# hex_bin_eeprom_display.net
KiCad netlist of a schematic drawn in EAGLE
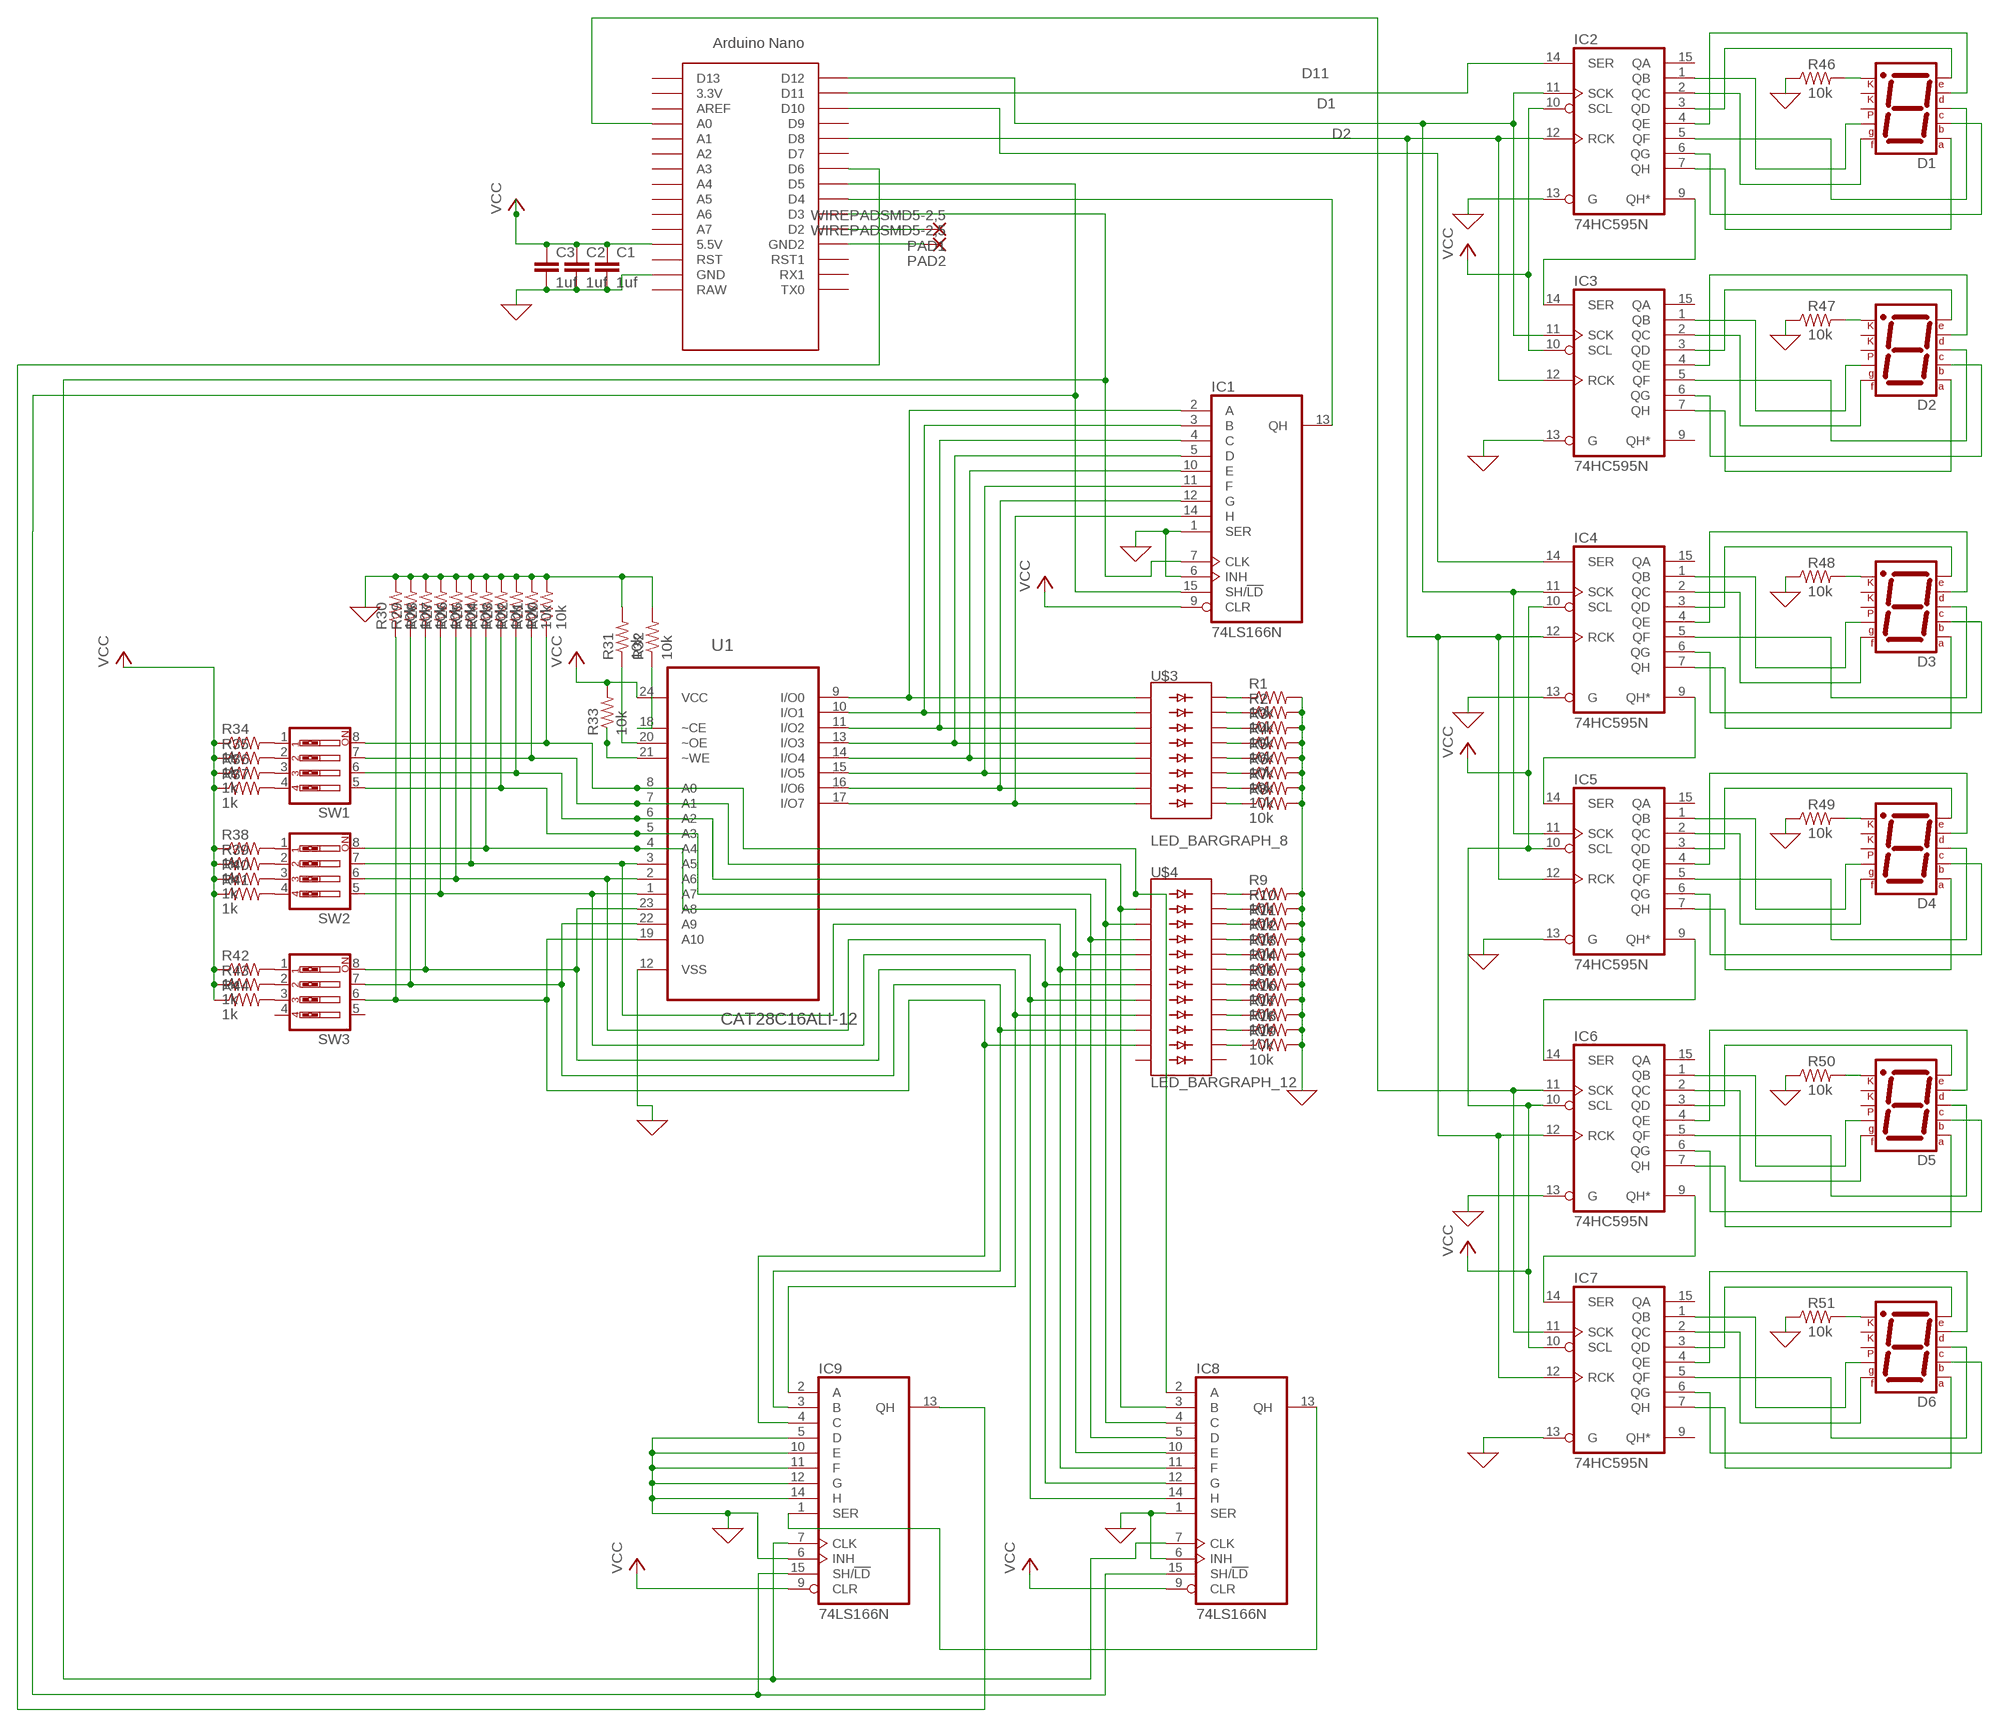
[diagram p0: schematic, sheet 1]

(export (version "E")
  (design (tool "Eeschema 10.0.6"))
  (components
    (comp (ref "C1")
      (value "1uf")
      (footprint "eagle-import:C5B3")
      (libsource (lib "eagle-import") (part "C5/3"))
    )
    (comp (ref "C2")
      (value "1uf")
      (footprint "eagle-import:C5B3")
      (libsource (lib "eagle-import") (part "C5/3"))
    )
    (comp (ref "C3")
      (value "1uf")
      (footprint "eagle-import:C5B3")
      (libsource (lib "eagle-import") (part "C5/3"))
    )
    (comp (ref "D1")
      (value "7SEG-CK")
      (footprint "eagle-import:7SEG-13")
      (libsource (lib "eagle-import") (part "7SEG-CK"))
    )
    (comp (ref "D2")
      (value "7SEG-CK")
      (footprint "eagle-import:7SEG-13")
      (libsource (lib "eagle-import") (part "7SEG-CK"))
    )
    (comp (ref "D3")
      (value "7SEG-CK")
      (footprint "eagle-import:7SEG-13")
      (libsource (lib "eagle-import") (part "7SEG-CK"))
    )
    (comp (ref "D4")
      (value "7SEG-CK")
      (footprint "eagle-import:7SEG-13")
      (libsource (lib "eagle-import") (part "7SEG-CK"))
    )
    (comp (ref "D5")
      (value "7SEG-CK")
      (footprint "eagle-import:7SEG-13")
      (libsource (lib "eagle-import") (part "7SEG-CK"))
    )
    (comp (ref "D6")
      (value "7SEG-CK")
      (footprint "eagle-import:7SEG-13")
      (libsource (lib "eagle-import") (part "7SEG-CK"))
    )
    (comp (ref "IC1")
      (value "74LS166N")
      (footprint "eagle-import:DIL16")
      (libsource (lib "eagle-import") (part "74166NLS"))
    )
    (comp (ref "IC2")
      (value "74HC595N")
      (footprint "eagle-import:DIL16")
      (libsource (lib "eagle-import") (part "74595NHC"))
    )
    (comp (ref "IC3")
      (value "74HC595N")
      (footprint "eagle-import:DIL16")
      (libsource (lib "eagle-import") (part "74595NHC"))
    )
    (comp (ref "IC4")
      (value "74HC595N")
      (footprint "eagle-import:DIL16")
      (libsource (lib "eagle-import") (part "74595NHC"))
    )
    (comp (ref "IC5")
      (value "74HC595N")
      (footprint "eagle-import:DIL16")
      (libsource (lib "eagle-import") (part "74595NHC"))
    )
    (comp (ref "IC6")
      (value "74HC595N")
      (footprint "eagle-import:DIL16")
      (libsource (lib "eagle-import") (part "74595NHC"))
    )
    (comp (ref "IC7")
      (value "74HC595N")
      (footprint "eagle-import:DIL16")
      (libsource (lib "eagle-import") (part "74595NHC"))
    )
    (comp (ref "IC8")
      (value "74LS166N")
      (footprint "eagle-import:DIL16")
      (libsource (lib "eagle-import") (part "74166NLS"))
    )
    (comp (ref "IC9")
      (value "74LS166N")
      (footprint "eagle-import:DIL16")
      (libsource (lib "eagle-import") (part "74166NLS"))
    )
    (comp (ref "PAD1")
      (value "WIREPADSMD5-2,5")
      (footprint "eagle-import:5-2,5")
      (libsource (lib "eagle-import") (part "WIREPADSMD5-2,5"))
    )
    (comp (ref "PAD2")
      (value "WIREPADSMD5-2,5")
      (footprint "eagle-import:5-2,5")
      (libsource (lib "eagle-import") (part "WIREPADSMD5-2,5"))
    )
    (comp (ref "R1")
      (value "10k")
      (footprint "eagle-import:0204_7")
      (libsource (lib "eagle-import") (part "R-US_0204/7"))
    )
    (comp (ref "R2")
      (value "10k")
      (footprint "eagle-import:0204_7")
      (libsource (lib "eagle-import") (part "R-US_0204/7"))
    )
    (comp (ref "R3")
      (value "10k")
      (footprint "eagle-import:0204_7")
      (libsource (lib "eagle-import") (part "R-US_0204/7"))
    )
    (comp (ref "R4")
      (value "10k")
      (footprint "eagle-import:0204_7")
      (libsource (lib "eagle-import") (part "R-US_0204/7"))
    )
    (comp (ref "R5")
      (value "10k")
      (footprint "eagle-import:0204_7")
      (libsource (lib "eagle-import") (part "R-US_0204/7"))
    )
    (comp (ref "R6")
      (value "10k")
      (footprint "eagle-import:0204_7")
      (libsource (lib "eagle-import") (part "R-US_0204/7"))
    )
    (comp (ref "R7")
      (value "10k")
      (footprint "eagle-import:0204_7")
      (libsource (lib "eagle-import") (part "R-US_0204/7"))
    )
    (comp (ref "R8")
      (value "10k")
      (footprint "eagle-import:0204_7")
      (libsource (lib "eagle-import") (part "R-US_0204/7"))
    )
    (comp (ref "R9")
      (value "10k")
      (footprint "eagle-import:0204_7")
      (libsource (lib "eagle-import") (part "R-US_0204/7"))
    )
    (comp (ref "R10")
      (value "10k")
      (footprint "eagle-import:0204_7")
      (libsource (lib "eagle-import") (part "R-US_0204/7"))
    )
    (comp (ref "R11")
      (value "10k")
      (footprint "eagle-import:0204_7")
      (libsource (lib "eagle-import") (part "R-US_0204/7"))
    )
    (comp (ref "R12")
      (value "10k")
      (footprint "eagle-import:0204_7")
      (libsource (lib "eagle-import") (part "R-US_0204/7"))
    )
    (comp (ref "R13")
      (value "10k")
      (footprint "eagle-import:0204_7")
      (libsource (lib "eagle-import") (part "R-US_0204/7"))
    )
    (comp (ref "R14")
      (value "10k")
      (footprint "eagle-import:0204_7")
      (libsource (lib "eagle-import") (part "R-US_0204/7"))
    )
    (comp (ref "R15")
      (value "10k")
      (footprint "eagle-import:0204_7")
      (libsource (lib "eagle-import") (part "R-US_0204/7"))
    )
    (comp (ref "R16")
      (value "10k")
      (footprint "eagle-import:0204_7")
      (libsource (lib "eagle-import") (part "R-US_0204/7"))
    )
    (comp (ref "R17")
      (value "10k")
      (footprint "eagle-import:0204_7")
      (libsource (lib "eagle-import") (part "R-US_0204/7"))
    )
    (comp (ref "R18")
      (value "10k")
      (footprint "eagle-import:0204_7")
      (libsource (lib "eagle-import") (part "R-US_0204/7"))
    )
    (comp (ref "R19")
      (value "10k")
      (footprint "eagle-import:0204_7")
      (libsource (lib "eagle-import") (part "R-US_0204/7"))
    )
    (comp (ref "R20")
      (value "10k")
      (footprint "eagle-import:0204_7")
      (libsource (lib "eagle-import") (part "R-US_0204/7"))
    )
    (comp (ref "R21")
      (value "10k")
      (footprint "eagle-import:0204_7")
      (libsource (lib "eagle-import") (part "R-US_0204/7"))
    )
    (comp (ref "R22")
      (value "10k")
      (footprint "eagle-import:0204_7")
      (libsource (lib "eagle-import") (part "R-US_0204/7"))
    )
    (comp (ref "R23")
      (value "10k")
      (footprint "eagle-import:0204_7")
      (libsource (lib "eagle-import") (part "R-US_0204/7"))
    )
    (comp (ref "R24")
      (value "10k")
      (footprint "eagle-import:0204_7")
      (libsource (lib "eagle-import") (part "R-US_0204/7"))
    )
    (comp (ref "R25")
      (value "10k")
      (footprint "eagle-import:0204_7")
      (libsource (lib "eagle-import") (part "R-US_0204/7"))
    )
    (comp (ref "R26")
      (value "10k")
      (footprint "eagle-import:0204_7")
      (libsource (lib "eagle-import") (part "R-US_0204/7"))
    )
    (comp (ref "R27")
      (value "10k")
      (footprint "eagle-import:0204_7")
      (libsource (lib "eagle-import") (part "R-US_0204/7"))
    )
    (comp (ref "R28")
      (value "10k")
      (footprint "eagle-import:0204_7")
      (libsource (lib "eagle-import") (part "R-US_0204/7"))
    )
    (comp (ref "R29")
      (value "10k")
      (footprint "eagle-import:0204_7")
      (libsource (lib "eagle-import") (part "R-US_0204/7"))
    )
    (comp (ref "R30")
      (value "10k")
      (footprint "eagle-import:0204_7")
      (libsource (lib "eagle-import") (part "R-US_0204/7"))
    )
    (comp (ref "R31")
      (value "10k")
      (footprint "eagle-import:0204_7")
      (libsource (lib "eagle-import") (part "R-US_0204/7"))
    )
    (comp (ref "R32")
      (value "10k")
      (footprint "eagle-import:0204_7")
      (libsource (lib "eagle-import") (part "R-US_0204/7"))
    )
    (comp (ref "R33")
      (value "10k")
      (footprint "eagle-import:0204_7")
      (libsource (lib "eagle-import") (part "R-US_0204/7"))
    )
    (comp (ref "R34")
      (value "1k")
      (footprint "eagle-import:0204_7")
      (libsource (lib "eagle-import") (part "R-US_0204/7"))
    )
    (comp (ref "R35")
      (value "1k")
      (footprint "eagle-import:0204_7")
      (libsource (lib "eagle-import") (part "R-US_0204/7"))
    )
    (comp (ref "R36")
      (value "1k")
      (footprint "eagle-import:0204_7")
      (libsource (lib "eagle-import") (part "R-US_0204/7"))
    )
    (comp (ref "R37")
      (value "1k")
      (footprint "eagle-import:0204_7")
      (libsource (lib "eagle-import") (part "R-US_0204/7"))
    )
    (comp (ref "R38")
      (value "1k")
      (footprint "eagle-import:0204_7")
      (libsource (lib "eagle-import") (part "R-US_0204/7"))
    )
    (comp (ref "R39")
      (value "1k")
      (footprint "eagle-import:0204_7")
      (libsource (lib "eagle-import") (part "R-US_0204/7"))
    )
    (comp (ref "R40")
      (value "1k")
      (footprint "eagle-import:0204_7")
      (libsource (lib "eagle-import") (part "R-US_0204/7"))
    )
    (comp (ref "R41")
      (value "1k")
      (footprint "eagle-import:0204_7")
      (libsource (lib "eagle-import") (part "R-US_0204/7"))
    )
    (comp (ref "R42")
      (value "1k")
      (footprint "eagle-import:0204_7")
      (libsource (lib "eagle-import") (part "R-US_0204/7"))
    )
    (comp (ref "R43")
      (value "1k")
      (footprint "eagle-import:0204_7")
      (libsource (lib "eagle-import") (part "R-US_0204/7"))
    )
    (comp (ref "R44")
      (value "1k")
      (footprint "eagle-import:0204_7")
      (libsource (lib "eagle-import") (part "R-US_0204/7"))
    )
    (comp (ref "R46")
      (value "10k")
      (footprint "eagle-import:0204_7")
      (libsource (lib "eagle-import") (part "R-US_0204/7"))
    )
    (comp (ref "R47")
      (value "10k")
      (footprint "eagle-import:0204_7")
      (libsource (lib "eagle-import") (part "R-US_0204/7"))
    )
    (comp (ref "R48")
      (value "10k")
      (footprint "eagle-import:0204_7")
      (libsource (lib "eagle-import") (part "R-US_0204/7"))
    )
    (comp (ref "R49")
      (value "10k")
      (footprint "eagle-import:0204_7")
      (libsource (lib "eagle-import") (part "R-US_0204/7"))
    )
    (comp (ref "R50")
      (value "10k")
      (footprint "eagle-import:0204_7")
      (libsource (lib "eagle-import") (part "R-US_0204/7"))
    )
    (comp (ref "R51")
      (value "10k")
      (footprint "eagle-import:0204_7")
      (libsource (lib "eagle-import") (part "R-US_0204/7"))
    )
    (comp (ref "SW1")
      (value "SW_DIP-4")
      (footprint "eagle-import:EDG-04")
      (libsource (lib "eagle-import") (part "SW_DIP-4"))
    )
    (comp (ref "SW2")
      (value "SW_DIP-4")
      (footprint "eagle-import:EDG-04")
      (libsource (lib "eagle-import") (part "SW_DIP-4"))
    )
    (comp (ref "SW3")
      (value "SW_DIP-4")
      (footprint "eagle-import:EDG-04")
      (libsource (lib "eagle-import") (part "SW_DIP-4"))
    )
    (comp (ref "U$1")
      (value "NANO")
      (footprint "eagle-import:NANO")
      (libsource (lib "eagle-import") (part "NANO"))
    )
    (comp (ref "U$3")
      (value "LED_BARGRAPH_8")
      (footprint "eagle-import:LED_BARGRAPH_8")
      (libsource (lib "eagle-import") (part "LED_BARGRAPH_8"))
    )
    (comp (ref "U$4")
      (value "LED_BARGRAPH_12")
      (footprint "eagle-import:LED_BARGRAPH_12")
      (libsource (lib "eagle-import") (part "LED_BARGRAPH_12"))
    )
    (comp (ref "U1")
      (value "CAT28C16ALI-12")
      (footprint "eagle-import:DIP254P1524X635-24")
      (fields (field (name "MF") "ON Semiconductor") (field (name "MP") "CAT28C16ALI12"))
      (libsource (lib "eagle-import") (part "CAT28C16ALI-12"))
    )
  )
  (nets
    (net (code "1") (name "/D1") (class "Default")
      (node (ref "IC2") (pin "11") (pinfunction "SCK_11") (pintype "input"))
      (node (ref "IC3") (pin "11") (pinfunction "SCK_11") (pintype "input"))
      (node (ref "IC4") (pin "11") (pinfunction "SCK_11") (pintype "input"))
      (node (ref "IC5") (pin "11") (pinfunction "SCK_11") (pintype "input"))
      (node (ref "U$1") (pin "D12") (pinfunction "D12_D12") (pintype "bidirectional"))
    )
    (net (code "2") (name "/D2") (class "Default")
      (node (ref "IC2") (pin "12") (pinfunction "RCK_12") (pintype "input"))
      (node (ref "IC3") (pin "12") (pinfunction "RCK_12") (pintype "input"))
      (node (ref "IC4") (pin "12") (pinfunction "RCK_12") (pintype "input"))
      (node (ref "IC5") (pin "12") (pinfunction "RCK_12") (pintype "input"))
      (node (ref "IC6") (pin "12") (pinfunction "RCK_12") (pintype "input"))
      (node (ref "IC7") (pin "12") (pinfunction "RCK_12") (pintype "input"))
      (node (ref "U$1") (pin "D8") (pinfunction "D8_D8") (pintype "bidirectional"))
    )
    (net (code "3") (name "/D11") (class "Default")
      (node (ref "IC2") (pin "14") (pinfunction "SER_14") (pintype "input"))
      (node (ref "U$1") (pin "D11") (pinfunction "D11_D11") (pintype "bidirectional"))
    )
    (net (code "4") (name "GND") (class "Default")
      (node (ref "C1") (pin "2") (pinfunction "2_2") (pintype "passive"))
      (node (ref "C2") (pin "2") (pinfunction "2_2") (pintype "passive"))
      (node (ref "C3") (pin "2") (pinfunction "2_2") (pintype "passive"))
      (node (ref "IC1") (pin "1") (pinfunction "SER_1") (pintype "input"))
      (node (ref "IC1") (pin "6") (pinfunction "INH_6") (pintype "input"))
      (node (ref "IC2") (pin "13") (pinfunction "G_13") (pintype "input"))
      (node (ref "IC3") (pin "13") (pinfunction "G_13") (pintype "input"))
      (node (ref "IC4") (pin "13") (pinfunction "G_13") (pintype "input"))
      (node (ref "IC5") (pin "13") (pinfunction "G_13") (pintype "input"))
      (node (ref "IC6") (pin "13") (pinfunction "G_13") (pintype "input"))
      (node (ref "IC7") (pin "13") (pinfunction "G_13") (pintype "input"))
      (node (ref "IC8") (pin "1") (pinfunction "SER_1") (pintype "input"))
      (node (ref "IC8") (pin "6") (pinfunction "INH_6") (pintype "input"))
      (node (ref "IC9") (pin "10") (pinfunction "E_10") (pintype "input"))
      (node (ref "IC9") (pin "11") (pinfunction "F_11") (pintype "input"))
      (node (ref "IC9") (pin "12") (pinfunction "G_12") (pintype "input"))
      (node (ref "IC9") (pin "14") (pinfunction "H_14") (pintype "input"))
      (node (ref "IC9") (pin "5") (pinfunction "D_5") (pintype "input"))
      (node (ref "IC9") (pin "6") (pinfunction "INH_6") (pintype "input"))
      (node (ref "R1") (pin "2") (pinfunction "2_2") (pintype "passive"))
      (node (ref "R10") (pin "2") (pinfunction "2_2") (pintype "passive"))
      (node (ref "R11") (pin "2") (pinfunction "2_2") (pintype "passive"))
      (node (ref "R12") (pin "2") (pinfunction "2_2") (pintype "passive"))
      (node (ref "R13") (pin "2") (pinfunction "2_2") (pintype "passive"))
      (node (ref "R14") (pin "2") (pinfunction "2_2") (pintype "passive"))
      (node (ref "R15") (pin "2") (pinfunction "2_2") (pintype "passive"))
      (node (ref "R16") (pin "2") (pinfunction "2_2") (pintype "passive"))
      (node (ref "R17") (pin "2") (pinfunction "2_2") (pintype "passive"))
      (node (ref "R18") (pin "2") (pinfunction "2_2") (pintype "passive"))
      (node (ref "R19") (pin "2") (pinfunction "2_2") (pintype "passive"))
      (node (ref "R2") (pin "2") (pinfunction "2_2") (pintype "passive"))
      (node (ref "R20") (pin "2") (pinfunction "2_2") (pintype "passive"))
      (node (ref "R21") (pin "2") (pinfunction "2_2") (pintype "passive"))
      (node (ref "R22") (pin "2") (pinfunction "2_2") (pintype "passive"))
      (node (ref "R23") (pin "2") (pinfunction "2_2") (pintype "passive"))
      (node (ref "R24") (pin "2") (pinfunction "2_2") (pintype "passive"))
      (node (ref "R25") (pin "2") (pinfunction "2_2") (pintype "passive"))
      (node (ref "R26") (pin "2") (pinfunction "2_2") (pintype "passive"))
      (node (ref "R27") (pin "2") (pinfunction "2_2") (pintype "passive"))
      (node (ref "R28") (pin "2") (pinfunction "2_2") (pintype "passive"))
      (node (ref "R29") (pin "2") (pinfunction "2_2") (pintype "passive"))
      (node (ref "R3") (pin "2") (pinfunction "2_2") (pintype "passive"))
      (node (ref "R30") (pin "2") (pinfunction "2_2") (pintype "passive"))
      (node (ref "R31") (pin "2") (pinfunction "2_2") (pintype "passive"))
      (node (ref "R32") (pin "2") (pinfunction "2_2") (pintype "passive"))
      (node (ref "R4") (pin "2") (pinfunction "2_2") (pintype "passive"))
      (node (ref "R46") (pin "1") (pinfunction "1_1") (pintype "passive"))
      (node (ref "R47") (pin "1") (pinfunction "1_1") (pintype "passive"))
      (node (ref "R48") (pin "1") (pinfunction "1_1") (pintype "passive"))
      (node (ref "R49") (pin "1") (pinfunction "1_1") (pintype "passive"))
      (node (ref "R5") (pin "2") (pinfunction "2_2") (pintype "passive"))
      (node (ref "R50") (pin "1") (pinfunction "1_1") (pintype "passive"))
      (node (ref "R51") (pin "1") (pinfunction "1_1") (pintype "passive"))
      (node (ref "R6") (pin "2") (pinfunction "2_2") (pintype "passive"))
      (node (ref "R7") (pin "2") (pinfunction "2_2") (pintype "passive"))
      (node (ref "R8") (pin "2") (pinfunction "2_2") (pintype "passive"))
      (node (ref "R9") (pin "2") (pinfunction "2_2") (pintype "passive"))
      (node (ref "U$1") (pin "GND") (pinfunction "GND_GND") (pintype "bidirectional"))
      (node (ref "U1") (pin "12") (pinfunction "VSS_12") (pintype "power_in"))
    )
    (net (code "5") (name "Net-(D1-A)") (class "Default")
      (node (ref "D1") (pin "7") (pinfunction "A_7") (pintype "passive"))
      (node (ref "IC2") (pin "7") (pinfunction "QH_7") (pintype "tri_state"))
    )
    (net (code "6") (name "Net-(D1-B)") (class "Default")
      (node (ref "D1") (pin "6") (pinfunction "B_6") (pintype "passive"))
      (node (ref "IC2") (pin "6") (pinfunction "QG_6") (pintype "tri_state"))
    )
    (net (code "7") (name "Net-(D1-C)") (class "Default")
      (node (ref "D1") (pin "4") (pinfunction "C_4") (pintype "passive"))
      (node (ref "IC2") (pin "5") (pinfunction "QF_5") (pintype "tri_state"))
    )
    (net (code "8") (name "Net-(D1-CK2)") (class "Default")
      (node (ref "D1") (pin "8") (pinfunction "CK2_8") (pintype "passive"))
      (node (ref "R46") (pin "2") (pinfunction "2_2") (pintype "passive"))
    )
    (net (code "9") (name "Net-(D1-D)") (class "Default")
      (node (ref "D1") (pin "2") (pinfunction "D_2") (pintype "passive"))
      (node (ref "IC2") (pin "4") (pinfunction "QE_4") (pintype "tri_state"))
    )
    (net (code "10") (name "Net-(D1-E)") (class "Default")
      (node (ref "D1") (pin "1") (pinfunction "E_1") (pintype "passive"))
      (node (ref "IC2") (pin "3") (pinfunction "QD_3") (pintype "tri_state"))
    )
    (net (code "11") (name "Net-(D1-F)") (class "Default")
      (node (ref "D1") (pin "9") (pinfunction "F_9") (pintype "passive"))
      (node (ref "IC2") (pin "2") (pinfunction "QC_2") (pintype "tri_state"))
    )
    (net (code "12") (name "Net-(D1-G)") (class "Default")
      (node (ref "D1") (pin "10") (pinfunction "G_10") (pintype "passive"))
      (node (ref "IC2") (pin "1") (pinfunction "QB_1") (pintype "tri_state"))
    )
    (net (code "13") (name "Net-(D2-A)") (class "Default")
      (node (ref "D2") (pin "7") (pinfunction "A_7") (pintype "passive"))
      (node (ref "IC3") (pin "7") (pinfunction "QH_7") (pintype "tri_state"))
    )
    (net (code "14") (name "Net-(D2-B)") (class "Default")
      (node (ref "D2") (pin "6") (pinfunction "B_6") (pintype "passive"))
      (node (ref "IC3") (pin "6") (pinfunction "QG_6") (pintype "tri_state"))
    )
    (net (code "15") (name "Net-(D2-C)") (class "Default")
      (node (ref "D2") (pin "4") (pinfunction "C_4") (pintype "passive"))
      (node (ref "IC3") (pin "5") (pinfunction "QF_5") (pintype "tri_state"))
    )
    (net (code "16") (name "Net-(D2-CK2)") (class "Default")
      (node (ref "D2") (pin "8") (pinfunction "CK2_8") (pintype "passive"))
      (node (ref "R47") (pin "2") (pinfunction "2_2") (pintype "passive"))
    )
    (net (code "17") (name "Net-(D2-D)") (class "Default")
      (node (ref "D2") (pin "2") (pinfunction "D_2") (pintype "passive"))
      (node (ref "IC3") (pin "4") (pinfunction "QE_4") (pintype "tri_state"))
    )
    (net (code "18") (name "Net-(D2-E)") (class "Default")
      (node (ref "D2") (pin "1") (pinfunction "E_1") (pintype "passive"))
      (node (ref "IC3") (pin "3") (pinfunction "QD_3") (pintype "tri_state"))
    )
    (net (code "19") (name "Net-(D2-F)") (class "Default")
      (node (ref "D2") (pin "9") (pinfunction "F_9") (pintype "passive"))
      (node (ref "IC3") (pin "2") (pinfunction "QC_2") (pintype "tri_state"))
    )
    (net (code "20") (name "Net-(D2-G)") (class "Default")
      (node (ref "D2") (pin "10") (pinfunction "G_10") (pintype "passive"))
      (node (ref "IC3") (pin "1") (pinfunction "QB_1") (pintype "tri_state"))
    )
    (net (code "21") (name "Net-(D3-A)") (class "Default")
      (node (ref "D3") (pin "7") (pinfunction "A_7") (pintype "passive"))
      (node (ref "IC4") (pin "7") (pinfunction "QH_7") (pintype "tri_state"))
    )
    (net (code "22") (name "Net-(D3-B)") (class "Default")
      (node (ref "D3") (pin "6") (pinfunction "B_6") (pintype "passive"))
      (node (ref "IC4") (pin "6") (pinfunction "QG_6") (pintype "tri_state"))
    )
    (net (code "23") (name "Net-(D3-C)") (class "Default")
      (node (ref "D3") (pin "4") (pinfunction "C_4") (pintype "passive"))
      (node (ref "IC4") (pin "5") (pinfunction "QF_5") (pintype "tri_state"))
    )
    (net (code "24") (name "Net-(D3-CK2)") (class "Default")
      (node (ref "D3") (pin "8") (pinfunction "CK2_8") (pintype "passive"))
      (node (ref "R48") (pin "2") (pinfunction "2_2") (pintype "passive"))
    )
    (net (code "25") (name "Net-(D3-D)") (class "Default")
      (node (ref "D3") (pin "2") (pinfunction "D_2") (pintype "passive"))
      (node (ref "IC4") (pin "4") (pinfunction "QE_4") (pintype "tri_state"))
    )
    (net (code "26") (name "Net-(D3-E)") (class "Default")
      (node (ref "D3") (pin "1") (pinfunction "E_1") (pintype "passive"))
      (node (ref "IC4") (pin "3") (pinfunction "QD_3") (pintype "tri_state"))
    )
    (net (code "27") (name "Net-(D3-F)") (class "Default")
      (node (ref "D3") (pin "9") (pinfunction "F_9") (pintype "passive"))
      (node (ref "IC4") (pin "2") (pinfunction "QC_2") (pintype "tri_state"))
    )
    (net (code "28") (name "Net-(D3-G)") (class "Default")
      (node (ref "D3") (pin "10") (pinfunction "G_10") (pintype "passive"))
      (node (ref "IC4") (pin "1") (pinfunction "QB_1") (pintype "tri_state"))
    )
    (net (code "29") (name "Net-(D4-A)") (class "Default")
      (node (ref "D4") (pin "7") (pinfunction "A_7") (pintype "passive"))
      (node (ref "IC5") (pin "7") (pinfunction "QH_7") (pintype "tri_state"))
    )
    (net (code "30") (name "Net-(D4-B)") (class "Default")
      (node (ref "D4") (pin "6") (pinfunction "B_6") (pintype "passive"))
      (node (ref "IC5") (pin "6") (pinfunction "QG_6") (pintype "tri_state"))
    )
    (net (code "31") (name "Net-(D4-C)") (class "Default")
      (node (ref "D4") (pin "4") (pinfunction "C_4") (pintype "passive"))
      (node (ref "IC5") (pin "5") (pinfunction "QF_5") (pintype "tri_state"))
    )
    (net (code "32") (name "Net-(D4-CK2)") (class "Default")
      (node (ref "D4") (pin "8") (pinfunction "CK2_8") (pintype "passive"))
      (node (ref "R49") (pin "2") (pinfunction "2_2") (pintype "passive"))
    )
    (net (code "33") (name "Net-(D4-D)") (class "Default")
      (node (ref "D4") (pin "2") (pinfunction "D_2") (pintype "passive"))
      (node (ref "IC5") (pin "4") (pinfunction "QE_4") (pintype "tri_state"))
    )
    (net (code "34") (name "Net-(D4-E)") (class "Default")
      (node (ref "D4") (pin "1") (pinfunction "E_1") (pintype "passive"))
      (node (ref "IC5") (pin "3") (pinfunction "QD_3") (pintype "tri_state"))
    )
    (net (code "35") (name "Net-(D4-F)") (class "Default")
      (node (ref "D4") (pin "9") (pinfunction "F_9") (pintype "passive"))
      (node (ref "IC5") (pin "2") (pinfunction "QC_2") (pintype "tri_state"))
    )
    (net (code "36") (name "Net-(D4-G)") (class "Default")
      (node (ref "D4") (pin "10") (pinfunction "G_10") (pintype "passive"))
      (node (ref "IC5") (pin "1") (pinfunction "QB_1") (pintype "tri_state"))
    )
    (net (code "37") (name "Net-(D5-A)") (class "Default")
      (node (ref "D5") (pin "7") (pinfunction "A_7") (pintype "passive"))
      (node (ref "IC6") (pin "7") (pinfunction "QH_7") (pintype "tri_state"))
    )
    (net (code "38") (name "Net-(D5-B)") (class "Default")
      (node (ref "D5") (pin "6") (pinfunction "B_6") (pintype "passive"))
      (node (ref "IC6") (pin "6") (pinfunction "QG_6") (pintype "tri_state"))
    )
    (net (code "39") (name "Net-(D5-C)") (class "Default")
      (node (ref "D5") (pin "4") (pinfunction "C_4") (pintype "passive"))
      (node (ref "IC6") (pin "5") (pinfunction "QF_5") (pintype "tri_state"))
    )
    (net (code "40") (name "Net-(D5-CK2)") (class "Default")
      (node (ref "D5") (pin "8") (pinfunction "CK2_8") (pintype "passive"))
      (node (ref "R50") (pin "2") (pinfunction "2_2") (pintype "passive"))
    )
    (net (code "41") (name "Net-(D5-D)") (class "Default")
      (node (ref "D5") (pin "2") (pinfunction "D_2") (pintype "passive"))
      (node (ref "IC6") (pin "4") (pinfunction "QE_4") (pintype "tri_state"))
    )
    (net (code "42") (name "Net-(D5-E)") (class "Default")
      (node (ref "D5") (pin "1") (pinfunction "E_1") (pintype "passive"))
      (node (ref "IC6") (pin "3") (pinfunction "QD_3") (pintype "tri_state"))
    )
    (net (code "43") (name "Net-(D5-F)") (class "Default")
      (node (ref "D5") (pin "9") (pinfunction "F_9") (pintype "passive"))
      (node (ref "IC6") (pin "2") (pinfunction "QC_2") (pintype "tri_state"))
    )
    (net (code "44") (name "Net-(D5-G)") (class "Default")
      (node (ref "D5") (pin "10") (pinfunction "G_10") (pintype "passive"))
      (node (ref "IC6") (pin "1") (pinfunction "QB_1") (pintype "tri_state"))
    )
    (net (code "45") (name "Net-(D6-A)") (class "Default")
      (node (ref "D6") (pin "7") (pinfunction "A_7") (pintype "passive"))
      (node (ref "IC7") (pin "7") (pinfunction "QH_7") (pintype "tri_state"))
    )
    (net (code "46") (name "Net-(D6-B)") (class "Default")
      (node (ref "D6") (pin "6") (pinfunction "B_6") (pintype "passive"))
      (node (ref "IC7") (pin "6") (pinfunction "QG_6") (pintype "tri_state"))
    )
    (net (code "47") (name "Net-(D6-C)") (class "Default")
      (node (ref "D6") (pin "4") (pinfunction "C_4") (pintype "passive"))
      (node (ref "IC7") (pin "5") (pinfunction "QF_5") (pintype "tri_state"))
    )
    (net (code "48") (name "Net-(D6-CK2)") (class "Default")
      (node (ref "D6") (pin "8") (pinfunction "CK2_8") (pintype "passive"))
      (node (ref "R51") (pin "2") (pinfunction "2_2") (pintype "passive"))
    )
    (net (code "49") (name "Net-(D6-D)") (class "Default")
      (node (ref "D6") (pin "2") (pinfunction "D_2") (pintype "passive"))
      (node (ref "IC7") (pin "4") (pinfunction "QE_4") (pintype "tri_state"))
    )
    (net (code "50") (name "Net-(D6-E)") (class "Default")
      (node (ref "D6") (pin "1") (pinfunction "E_1") (pintype "passive"))
      (node (ref "IC7") (pin "3") (pinfunction "QD_3") (pintype "tri_state"))
    )
    (net (code "51") (name "Net-(D6-F)") (class "Default")
      (node (ref "D6") (pin "9") (pinfunction "F_9") (pintype "passive"))
      (node (ref "IC7") (pin "2") (pinfunction "QC_2") (pintype "tri_state"))
    )
    (net (code "52") (name "Net-(D6-G)") (class "Default")
      (node (ref "D6") (pin "10") (pinfunction "G_10") (pintype "passive"))
      (node (ref "IC7") (pin "1") (pinfunction "QB_1") (pintype "tri_state"))
    )
    (net (code "53") (name "Net-(IC1A-A)") (class "Default")
      (node (ref "IC1") (pin "2") (pinfunction "A_2") (pintype "input"))
      (node (ref "U$3") (pin "1") (pinfunction "A_1") (pintype "passive"))
      (node (ref "U1") (pin "9") (pinfunction "I/O0_9") (pintype "bidirectional"))
    )
    (net (code "54") (name "Net-(IC1A-B)") (class "Default")
      (node (ref "IC1") (pin "3") (pinfunction "B_3") (pintype "input"))
      (node (ref "U$3") (pin "2") (pinfunction "A1_2") (pintype "passive"))
      (node (ref "U1") (pin "10") (pinfunction "I/O1_10") (pintype "bidirectional"))
    )
    (net (code "55") (name "Net-(IC1A-C)") (class "Default")
      (node (ref "IC1") (pin "4") (pinfunction "C_4") (pintype "input"))
      (node (ref "U$3") (pin "3") (pinfunction "A2_3") (pintype "passive"))
      (node (ref "U1") (pin "11") (pinfunction "I/O2_11") (pintype "bidirectional"))
    )
    (net (code "56") (name "Net-(IC1A-CLK)") (class "Default")
      (node (ref "IC1") (pin "7") (pinfunction "CLK_7") (pintype "input"))
      (node (ref "IC8") (pin "7") (pinfunction "CLK_7") (pintype "input"))
      (node (ref "IC9") (pin "7") (pinfunction "CLK_7") (pintype "input"))
      (node (ref "U$1") (pin "D3") (pinfunction "D3_D3") (pintype "bidirectional"))
    )
    (net (code "57") (name "Net-(IC1A-D)") (class "Default")
      (node (ref "IC1") (pin "5") (pinfunction "D_5") (pintype "input"))
      (node (ref "U$3") (pin "4") (pinfunction "A3_4") (pintype "passive"))
      (node (ref "U1") (pin "13") (pinfunction "I/O3_13") (pintype "bidirectional"))
    )
    (net (code "58") (name "Net-(IC1A-E)") (class "Default")
      (node (ref "IC1") (pin "10") (pinfunction "E_10") (pintype "input"))
      (node (ref "U$3") (pin "5") (pinfunction "A4_5") (pintype "passive"))
      (node (ref "U1") (pin "14") (pinfunction "I/O4_14") (pintype "bidirectional"))
    )
    (net (code "59") (name "Net-(IC1A-F)") (class "Default")
      (node (ref "IC1") (pin "11") (pinfunction "F_11") (pintype "input"))
      (node (ref "U$3") (pin "6") (pinfunction "A5_6") (pintype "passive"))
      (node (ref "U1") (pin "15") (pinfunction "I/O5_15") (pintype "bidirectional"))
    )
    (net (code "60") (name "Net-(IC1A-G)") (class "Default")
      (node (ref "IC1") (pin "12") (pinfunction "G_12") (pintype "input"))
      (node (ref "U$3") (pin "7") (pinfunction "A6_7") (pintype "passive"))
      (node (ref "U1") (pin "16") (pinfunction "I/O6_16") (pintype "bidirectional"))
    )
    (net (code "61") (name "Net-(IC1A-H)") (class "Default")
      (node (ref "IC1") (pin "14") (pinfunction "H_14") (pintype "input"))
      (node (ref "U$3") (pin "8") (pinfunction "A7_8") (pintype "passive"))
      (node (ref "U1") (pin "17") (pinfunction "I/O7_17") (pintype "bidirectional"))
    )
    (net (code "62") (name "Net-(IC1A-QH)") (class "Default")
      (node (ref "IC1") (pin "13") (pinfunction "QH_13") (pintype "output"))
      (node (ref "U$1") (pin "D4") (pinfunction "D4_D4") (pintype "bidirectional"))
    )
    (net (code "63") (name "Net-(IC1A-SH{slash}~{LD})") (class "Default")
      (node (ref "IC1") (pin "15") (pinfunction "SH/~{LD}_15") (pintype "input"))
      (node (ref "IC8") (pin "15") (pinfunction "SH/~{LD}_15") (pintype "input"))
      (node (ref "IC9") (pin "15") (pinfunction "SH/~{LD}_15") (pintype "input"))
      (node (ref "U$1") (pin "D5") (pinfunction "D5_D5") (pintype "bidirectional"))
    )
    (net (code "64") (name "Net-(IC2A-QH*)") (class "Default")
      (node (ref "IC2") (pin "9") (pinfunction "QH*_9") (pintype "tri_state"))
      (node (ref "IC3") (pin "14") (pinfunction "SER_14") (pintype "input"))
    )
    (net (code "65") (name "Net-(IC4A-QH*)") (class "Default")
      (node (ref "IC4") (pin "9") (pinfunction "QH*_9") (pintype "tri_state"))
      (node (ref "IC5") (pin "14") (pinfunction "SER_14") (pintype "input"))
    )
    (net (code "66") (name "Net-(IC4A-SER)") (class "Default")
      (node (ref "IC4") (pin "14") (pinfunction "SER_14") (pintype "input"))
      (node (ref "U$1") (pin "D10") (pinfunction "D10_D10") (pintype "bidirectional"))
    )
    (net (code "67") (name "Net-(IC5A-QH*)") (class "Default")
      (node (ref "IC5") (pin "9") (pinfunction "QH*_9") (pintype "tri_state"))
      (node (ref "IC6") (pin "14") (pinfunction "SER_14") (pintype "input"))
    )
    (net (code "68") (name "Net-(IC6A-QH*)") (class "Default")
      (node (ref "IC6") (pin "9") (pinfunction "QH*_9") (pintype "tri_state"))
      (node (ref "IC7") (pin "14") (pinfunction "SER_14") (pintype "input"))
    )
    (net (code "69") (name "Net-(IC6A-SCK)") (class "Default")
      (node (ref "IC6") (pin "11") (pinfunction "SCK_11") (pintype "input"))
      (node (ref "IC7") (pin "11") (pinfunction "SCK_11") (pintype "input"))
      (node (ref "U$1") (pin "A0") (pinfunction "A0_A0") (pintype "bidirectional"))
    )
    (net (code "70") (name "Net-(IC8A-A)") (class "Default")
      (node (ref "IC8") (pin "2") (pinfunction "A_2") (pintype "input"))
      (node (ref "R20") (pin "1") (pinfunction "1_1") (pintype "passive"))
      (node (ref "SW1") (pin "8") (pinfunction "8_8") (pintype "passive"))
      (node (ref "U$4") (pin "1") (pinfunction "A_1") (pintype "passive"))
      (node (ref "U1") (pin "8") (pinfunction "A0_8") (pintype "input"))
    )
    (net (code "71") (name "Net-(IC8A-B)") (class "Default")
      (node (ref "IC8") (pin "3") (pinfunction "B_3") (pintype "input"))
      (node (ref "R21") (pin "1") (pinfunction "1_1") (pintype "passive"))
      (node (ref "SW1") (pin "7") (pinfunction "7_7") (pintype "passive"))
      (node (ref "U$4") (pin "2") (pinfunction "A1_2") (pintype "passive"))
      (node (ref "U1") (pin "7") (pinfunction "A1_7") (pintype "input"))
    )
    (net (code "72") (name "Net-(IC8A-C)") (class "Default")
      (node (ref "IC8") (pin "4") (pinfunction "C_4") (pintype "input"))
      (node (ref "R22") (pin "1") (pinfunction "1_1") (pintype "passive"))
      (node (ref "SW1") (pin "6") (pinfunction "6_6") (pintype "passive"))
      (node (ref "U$4") (pin "3") (pinfunction "A2_3") (pintype "passive"))
      (node (ref "U1") (pin "6") (pinfunction "A2_6") (pintype "input"))
    )
    (net (code "73") (name "Net-(IC8A-D)") (class "Default")
      (node (ref "IC8") (pin "5") (pinfunction "D_5") (pintype "input"))
      (node (ref "R23") (pin "1") (pinfunction "1_1") (pintype "passive"))
      (node (ref "SW1") (pin "5") (pinfunction "5_5") (pintype "passive"))
      (node (ref "U$4") (pin "4") (pinfunction "A3_4") (pintype "passive"))
      (node (ref "U1") (pin "5") (pinfunction "A3_5") (pintype "input"))
    )
    (net (code "74") (name "Net-(IC8A-E)") (class "Default")
      (node (ref "IC8") (pin "10") (pinfunction "E_10") (pintype "input"))
      (node (ref "R24") (pin "1") (pinfunction "1_1") (pintype "passive"))
      (node (ref "SW2") (pin "8") (pinfunction "8_8") (pintype "passive"))
      (node (ref "U$4") (pin "5") (pinfunction "A4_5") (pintype "passive"))
      (node (ref "U1") (pin "4") (pinfunction "A4_4") (pintype "input"))
    )
    (net (code "75") (name "Net-(IC8A-F)") (class "Default")
      (node (ref "IC8") (pin "11") (pinfunction "F_11") (pintype "input"))
      (node (ref "R25") (pin "1") (pinfunction "1_1") (pintype "passive"))
      (node (ref "SW2") (pin "7") (pinfunction "7_7") (pintype "passive"))
      (node (ref "U$4") (pin "6") (pinfunction "A5_6") (pintype "passive"))
      (node (ref "U1") (pin "3") (pinfunction "A5_3") (pintype "input"))
    )
    (net (code "76") (name "Net-(IC8A-G)") (class "Default")
      (node (ref "IC8") (pin "12") (pinfunction "G_12") (pintype "input"))
      (node (ref "R26") (pin "1") (pinfunction "1_1") (pintype "passive"))
      (node (ref "SW2") (pin "6") (pinfunction "6_6") (pintype "passive"))
      (node (ref "U$4") (pin "7") (pinfunction "A6_7") (pintype "passive"))
      (node (ref "U1") (pin "2") (pinfunction "A6_2") (pintype "input"))
    )
    (net (code "77") (name "Net-(IC8A-H)") (class "Default")
      (node (ref "IC8") (pin "14") (pinfunction "H_14") (pintype "input"))
      (node (ref "R27") (pin "1") (pinfunction "1_1") (pintype "passive"))
      (node (ref "SW2") (pin "5") (pinfunction "5_5") (pintype "passive"))
      (node (ref "U$4") (pin "8") (pinfunction "A7_8") (pintype "passive"))
      (node (ref "U1") (pin "1") (pinfunction "A7_1") (pintype "input"))
    )
    (net (code "78") (name "Net-(IC8A-QH)") (class "Default")
      (node (ref "IC8") (pin "13") (pinfunction "QH_13") (pintype "output"))
      (node (ref "IC9") (pin "1") (pinfunction "SER_1") (pintype "input"))
    )
    (net (code "79") (name "Net-(IC9A-A)") (class "Default")
      (node (ref "IC9") (pin "2") (pinfunction "A_2") (pintype "input"))
      (node (ref "R28") (pin "1") (pinfunction "1_1") (pintype "passive"))
      (node (ref "SW3") (pin "8") (pinfunction "8_8") (pintype "passive"))
      (node (ref "U$4") (pin "9") (pinfunction "A8_9") (pintype "passive"))
      (node (ref "U1") (pin "23") (pinfunction "A8_23") (pintype "input"))
    )
    (net (code "80") (name "Net-(IC9A-B)") (class "Default")
      (node (ref "IC9") (pin "3") (pinfunction "B_3") (pintype "input"))
      (node (ref "R29") (pin "1") (pinfunction "1_1") (pintype "passive"))
      (node (ref "SW3") (pin "7") (pinfunction "7_7") (pintype "passive"))
      (node (ref "U$4") (pin "10") (pinfunction "A9_10") (pintype "passive"))
      (node (ref "U1") (pin "22") (pinfunction "A9_22") (pintype "input"))
    )
    (net (code "81") (name "Net-(IC9A-C)") (class "Default")
      (node (ref "IC9") (pin "4") (pinfunction "C_4") (pintype "input"))
      (node (ref "R30") (pin "1") (pinfunction "1_1") (pintype "passive"))
      (node (ref "SW3") (pin "6") (pinfunction "6_6") (pintype "passive"))
      (node (ref "U$4") (pin "11") (pinfunction "A10_11") (pintype "passive"))
      (node (ref "U1") (pin "19") (pinfunction "A10_19") (pintype "input"))
    )
    (net (code "82") (name "Net-(IC9A-QH)") (class "Default")
      (node (ref "IC9") (pin "13") (pinfunction "QH_13") (pintype "output"))
      (node (ref "U$1") (pin "D6") (pinfunction "D6_D6") (pintype "bidirectional"))
    )
    (net (code "83") (name "Net-(PAD1-P)") (class "Default")
      (node (ref "PAD1") (pin "1") (pinfunction "P_1") (pintype "passive"))
      (node (ref "U$1") (pin "D2") (pinfunction "D2_D2") (pintype "bidirectional"))
    )
    (net (code "84") (name "Net-(PAD2-P)") (class "Default")
      (node (ref "PAD2") (pin "1") (pinfunction "P_1") (pintype "passive"))
      (node (ref "U$1") (pin "GND1") (pinfunction "GND2_GND1") (pintype "bidirectional"))
    )
    (net (code "85") (name "Net-(R34-Pad2)") (class "Default")
      (node (ref "R34") (pin "2") (pinfunction "2_2") (pintype "passive"))
      (node (ref "SW1") (pin "1") (pinfunction "1_1") (pintype "passive"))
    )
    (net (code "86") (name "Net-(R35-Pad2)") (class "Default")
      (node (ref "R35") (pin "2") (pinfunction "2_2") (pintype "passive"))
      (node (ref "SW1") (pin "2") (pinfunction "2_2") (pintype "passive"))
    )
    (net (code "87") (name "Net-(R36-Pad2)") (class "Default")
      (node (ref "R36") (pin "2") (pinfunction "2_2") (pintype "passive"))
      (node (ref "SW1") (pin "3") (pinfunction "3_3") (pintype "passive"))
    )
    (net (code "88") (name "Net-(R37-Pad2)") (class "Default")
      (node (ref "R37") (pin "2") (pinfunction "2_2") (pintype "passive"))
      (node (ref "SW1") (pin "4") (pinfunction "4_4") (pintype "passive"))
    )
    (net (code "89") (name "Net-(R38-Pad2)") (class "Default")
      (node (ref "R38") (pin "2") (pinfunction "2_2") (pintype "passive"))
      (node (ref "SW2") (pin "1") (pinfunction "1_1") (pintype "passive"))
    )
    (net (code "90") (name "Net-(R39-Pad2)") (class "Default")
      (node (ref "R39") (pin "2") (pinfunction "2_2") (pintype "passive"))
      (node (ref "SW2") (pin "2") (pinfunction "2_2") (pintype "passive"))
    )
    (net (code "91") (name "Net-(R40-Pad2)") (class "Default")
      (node (ref "R40") (pin "2") (pinfunction "2_2") (pintype "passive"))
      (node (ref "SW2") (pin "3") (pinfunction "3_3") (pintype "passive"))
    )
    (net (code "92") (name "Net-(R41-Pad2)") (class "Default")
      (node (ref "R41") (pin "2") (pinfunction "2_2") (pintype "passive"))
      (node (ref "SW2") (pin "4") (pinfunction "4_4") (pintype "passive"))
    )
    (net (code "93") (name "Net-(R42-Pad2)") (class "Default")
      (node (ref "R42") (pin "2") (pinfunction "2_2") (pintype "passive"))
      (node (ref "SW3") (pin "1") (pinfunction "1_1") (pintype "passive"))
    )
    (net (code "94") (name "Net-(R43-Pad2)") (class "Default")
      (node (ref "R43") (pin "2") (pinfunction "2_2") (pintype "passive"))
      (node (ref "SW3") (pin "2") (pinfunction "2_2") (pintype "passive"))
    )
    (net (code "95") (name "Net-(R44-Pad2)") (class "Default")
      (node (ref "R44") (pin "2") (pinfunction "2_2") (pintype "passive"))
      (node (ref "SW3") (pin "3") (pinfunction "3_3") (pintype "passive"))
    )
    (net (code "96") (name "Net-(U$3-C)") (class "Default")
      (node (ref "R1") (pin "1") (pinfunction "1_1") (pintype "passive"))
      (node (ref "U$3") (pin "16") (pinfunction "C_16") (pintype "passive"))
    )
    (net (code "97") (name "Net-(U$3-C1)") (class "Default")
      (node (ref "R2") (pin "1") (pinfunction "1_1") (pintype "passive"))
      (node (ref "U$3") (pin "15") (pinfunction "C1_15") (pintype "passive"))
    )
    (net (code "98") (name "Net-(U$3-C2)") (class "Default")
      (node (ref "R3") (pin "1") (pinfunction "1_1") (pintype "passive"))
      (node (ref "U$3") (pin "14") (pinfunction "C2_14") (pintype "passive"))
    )
    (net (code "99") (name "Net-(U$3-C3)") (class "Default")
      (node (ref "R4") (pin "1") (pinfunction "1_1") (pintype "passive"))
      (node (ref "U$3") (pin "13") (pinfunction "C3_13") (pintype "passive"))
    )
    (net (code "100") (name "Net-(U$3-C4)") (class "Default")
      (node (ref "R5") (pin "1") (pinfunction "1_1") (pintype "passive"))
      (node (ref "U$3") (pin "12") (pinfunction "C4_12") (pintype "passive"))
    )
    (net (code "101") (name "Net-(U$3-C5)") (class "Default")
      (node (ref "R6") (pin "1") (pinfunction "1_1") (pintype "passive"))
      (node (ref "U$3") (pin "11") (pinfunction "C5_11") (pintype "passive"))
    )
    (net (code "102") (name "Net-(U$3-C6)") (class "Default")
      (node (ref "R7") (pin "1") (pinfunction "1_1") (pintype "passive"))
      (node (ref "U$3") (pin "10") (pinfunction "C6_10") (pintype "passive"))
    )
    (net (code "103") (name "Net-(U$3-C7)") (class "Default")
      (node (ref "R8") (pin "1") (pinfunction "1_1") (pintype "passive"))
      (node (ref "U$3") (pin "9") (pinfunction "C7_9") (pintype "passive"))
    )
    (net (code "104") (name "Net-(U$4-C)") (class "Default")
      (node (ref "R9") (pin "1") (pinfunction "1_1") (pintype "passive"))
      (node (ref "U$4") (pin "24") (pinfunction "C_24") (pintype "passive"))
    )
    (net (code "105") (name "Net-(U$4-C1)") (class "Default")
      (node (ref "R10") (pin "1") (pinfunction "1_1") (pintype "passive"))
      (node (ref "U$4") (pin "23") (pinfunction "C1_23") (pintype "passive"))
    )
    (net (code "106") (name "Net-(U$4-C2)") (class "Default")
      (node (ref "R11") (pin "1") (pinfunction "1_1") (pintype "passive"))
      (node (ref "U$4") (pin "22") (pinfunction "C2_22") (pintype "passive"))
    )
    (net (code "107") (name "Net-(U$4-C3)") (class "Default")
      (node (ref "R12") (pin "1") (pinfunction "1_1") (pintype "passive"))
      (node (ref "U$4") (pin "21") (pinfunction "C3_21") (pintype "passive"))
    )
    (net (code "108") (name "Net-(U$4-C4)") (class "Default")
      (node (ref "R13") (pin "1") (pinfunction "1_1") (pintype "passive"))
      (node (ref "U$4") (pin "20") (pinfunction "C4_20") (pintype "passive"))
    )
    (net (code "109") (name "Net-(U$4-C5)") (class "Default")
      (node (ref "R14") (pin "1") (pinfunction "1_1") (pintype "passive"))
      (node (ref "U$4") (pin "19") (pinfunction "C5_19") (pintype "passive"))
    )
    (net (code "110") (name "Net-(U$4-C6)") (class "Default")
      (node (ref "R15") (pin "1") (pinfunction "1_1") (pintype "passive"))
      (node (ref "U$4") (pin "18") (pinfunction "C6_18") (pintype "passive"))
    )
    (net (code "111") (name "Net-(U$4-C7)") (class "Default")
      (node (ref "R16") (pin "1") (pinfunction "1_1") (pintype "passive"))
      (node (ref "U$4") (pin "17") (pinfunction "C7_17") (pintype "passive"))
    )
    (net (code "112") (name "Net-(U$4-C8)") (class "Default")
      (node (ref "R17") (pin "1") (pinfunction "1_1") (pintype "passive"))
      (node (ref "U$4") (pin "16") (pinfunction "C8_16") (pintype "passive"))
    )
    (net (code "113") (name "Net-(U$4-C9)") (class "Default")
      (node (ref "R18") (pin "1") (pinfunction "1_1") (pintype "passive"))
      (node (ref "U$4") (pin "15") (pinfunction "C9_15") (pintype "passive"))
    )
    (net (code "114") (name "Net-(U$4-C10)") (class "Default")
      (node (ref "R19") (pin "1") (pinfunction "1_1") (pintype "passive"))
      (node (ref "U$4") (pin "14") (pinfunction "C10_14") (pintype "passive"))
    )
    (net (code "115") (name "Net-(U1-~{CE})") (class "Default")
      (node (ref "R32") (pin "1") (pinfunction "1_1") (pintype "passive"))
      (node (ref "U1") (pin "18") (pinfunction "~{CE}_18") (pintype "input"))
    )
    (net (code "116") (name "Net-(U1-~{OE})") (class "Default")
      (node (ref "R31") (pin "1") (pinfunction "1_1") (pintype "passive"))
      (node (ref "U1") (pin "20") (pinfunction "~{OE}_20") (pintype "input"))
    )
    (net (code "117") (name "Net-(U1-~{WE})") (class "Default")
      (node (ref "R33") (pin "1") (pinfunction "1_1") (pintype "passive"))
      (node (ref "U1") (pin "21") (pinfunction "~{WE}_21") (pintype "input"))
    )
    (net (code "118") (name "VCC") (class "Default")
      (node (ref "C1") (pin "1") (pinfunction "1_1") (pintype "passive"))
      (node (ref "C2") (pin "1") (pinfunction "1_1") (pintype "passive"))
      (node (ref "C3") (pin "1") (pinfunction "1_1") (pintype "passive"))
      (node (ref "IC1") (pin "9") (pinfunction "CLR_9") (pintype "input"))
      (node (ref "IC2") (pin "10") (pinfunction "SCL_10") (pintype "input"))
      (node (ref "IC3") (pin "10") (pinfunction "SCL_10") (pintype "input"))
      (node (ref "IC4") (pin "10") (pinfunction "SCL_10") (pintype "input"))
      (node (ref "IC5") (pin "10") (pinfunction "SCL_10") (pintype "input"))
      (node (ref "IC6") (pin "10") (pinfunction "SCL_10") (pintype "input"))
      (node (ref "IC7") (pin "10") (pinfunction "SCL_10") (pintype "input"))
      (node (ref "IC8") (pin "9") (pinfunction "CLR_9") (pintype "input"))
      (node (ref "IC9") (pin "9") (pinfunction "CLR_9") (pintype "input"))
      (node (ref "R33") (pin "2") (pinfunction "2_2") (pintype "passive"))
      (node (ref "R34") (pin "1") (pinfunction "1_1") (pintype "passive"))
      (node (ref "R35") (pin "1") (pinfunction "1_1") (pintype "passive"))
      (node (ref "R36") (pin "1") (pinfunction "1_1") (pintype "passive"))
      (node (ref "R37") (pin "1") (pinfunction "1_1") (pintype "passive"))
      (node (ref "R38") (pin "1") (pinfunction "1_1") (pintype "passive"))
      (node (ref "R39") (pin "1") (pinfunction "1_1") (pintype "passive"))
      (node (ref "R40") (pin "1") (pinfunction "1_1") (pintype "passive"))
      (node (ref "R41") (pin "1") (pinfunction "1_1") (pintype "passive"))
      (node (ref "R42") (pin "1") (pinfunction "1_1") (pintype "passive"))
      (node (ref "R43") (pin "1") (pinfunction "1_1") (pintype "passive"))
      (node (ref "R44") (pin "1") (pinfunction "1_1") (pintype "passive"))
      (node (ref "U$1") (pin "5V") (pinfunction "5.5V_5V") (pintype "bidirectional"))
      (node (ref "U1") (pin "24") (pinfunction "VCC_24") (pintype "power_in"))
    )
    (net (code "119") (name "unconnected-(D1-CK1-Pad3)") (class "Default")
      (node (ref "D1") (pin "3") (pinfunction "CK1_3") (pintype "passive"))
    )
    (net (code "120") (name "unconnected-(D1-DP-Pad5)") (class "Default")
      (node (ref "D1") (pin "5") (pinfunction "DP_5") (pintype "passive"))
    )
    (net (code "121") (name "unconnected-(D2-CK1-Pad3)") (class "Default")
      (node (ref "D2") (pin "3") (pinfunction "CK1_3") (pintype "passive"))
    )
    (net (code "122") (name "unconnected-(D2-DP-Pad5)") (class "Default")
      (node (ref "D2") (pin "5") (pinfunction "DP_5") (pintype "passive"))
    )
    (net (code "123") (name "unconnected-(D3-CK1-Pad3)") (class "Default")
      (node (ref "D3") (pin "3") (pinfunction "CK1_3") (pintype "passive"))
    )
    (net (code "124") (name "unconnected-(D3-DP-Pad5)") (class "Default")
      (node (ref "D3") (pin "5") (pinfunction "DP_5") (pintype "passive"))
    )
    (net (code "125") (name "unconnected-(D4-CK1-Pad3)") (class "Default")
      (node (ref "D4") (pin "3") (pinfunction "CK1_3") (pintype "passive"))
    )
    (net (code "126") (name "unconnected-(D4-DP-Pad5)") (class "Default")
      (node (ref "D4") (pin "5") (pinfunction "DP_5") (pintype "passive"))
    )
    (net (code "127") (name "unconnected-(D5-CK1-Pad3)") (class "Default")
      (node (ref "D5") (pin "3") (pinfunction "CK1_3") (pintype "passive"))
    )
    (net (code "128") (name "unconnected-(D5-DP-Pad5)") (class "Default")
      (node (ref "D5") (pin "5") (pinfunction "DP_5") (pintype "passive"))
    )
    (net (code "129") (name "unconnected-(D6-CK1-Pad3)") (class "Default")
      (node (ref "D6") (pin "3") (pinfunction "CK1_3") (pintype "passive"))
    )
    (net (code "130") (name "unconnected-(D6-DP-Pad5)") (class "Default")
      (node (ref "D6") (pin "5") (pinfunction "DP_5") (pintype "passive"))
    )
    (net (code "131") (name "unconnected-(IC2A-QA-Pad15)") (class "Default")
      (node (ref "IC2") (pin "15") (pinfunction "QA_15") (pintype "tri_state"))
    )
    (net (code "132") (name "unconnected-(IC3A-QA-Pad15)") (class "Default")
      (node (ref "IC3") (pin "15") (pinfunction "QA_15") (pintype "tri_state"))
    )
    (net (code "133") (name "unconnected-(IC3A-QH*-Pad9)") (class "Default")
      (node (ref "IC3") (pin "9") (pinfunction "QH*_9") (pintype "tri_state"))
    )
    (net (code "134") (name "unconnected-(IC4A-QA-Pad15)") (class "Default")
      (node (ref "IC4") (pin "15") (pinfunction "QA_15") (pintype "tri_state"))
    )
    (net (code "135") (name "unconnected-(IC5A-QA-Pad15)") (class "Default")
      (node (ref "IC5") (pin "15") (pinfunction "QA_15") (pintype "tri_state"))
    )
    (net (code "136") (name "unconnected-(IC6A-QA-Pad15)") (class "Default")
      (node (ref "IC6") (pin "15") (pinfunction "QA_15") (pintype "tri_state"))
    )
    (net (code "137") (name "unconnected-(IC7A-QA-Pad15)") (class "Default")
      (node (ref "IC7") (pin "15") (pinfunction "QA_15") (pintype "tri_state"))
    )
    (net (code "138") (name "unconnected-(IC7A-QH*-Pad9)") (class "Default")
      (node (ref "IC7") (pin "9") (pinfunction "QH*_9") (pintype "tri_state"))
    )
    (net (code "139") (name "unconnected-(SW3-Pad4)") (class "Default")
      (node (ref "SW3") (pin "4") (pinfunction "4_4") (pintype "passive"))
    )
    (net (code "140") (name "unconnected-(SW3-Pad5)") (class "Default")
      (node (ref "SW3") (pin "5") (pinfunction "5_5") (pintype "passive"))
    )
    (net (code "141") (name "unconnected-(U$1-Pad3.3V)") (class "Default")
      (node (ref "U$1") (pin "3.3V") (pinfunction "3.3V_3.3V") (pintype "bidirectional"))
    )
    (net (code "142") (name "unconnected-(U$1-PadA1)") (class "Default")
      (node (ref "U$1") (pin "A1") (pinfunction "A1_A1") (pintype "bidirectional"))
    )
    (net (code "143") (name "unconnected-(U$1-PadA2)") (class "Default")
      (node (ref "U$1") (pin "A2") (pinfunction "A2_A2") (pintype "bidirectional"))
    )
    (net (code "144") (name "unconnected-(U$1-PadA3)") (class "Default")
      (node (ref "U$1") (pin "A3") (pinfunction "A3_A3") (pintype "bidirectional"))
    )
    (net (code "145") (name "unconnected-(U$1-PadA4)") (class "Default")
      (node (ref "U$1") (pin "A4") (pinfunction "A4_A4") (pintype "bidirectional"))
    )
    (net (code "146") (name "unconnected-(U$1-PadA5)") (class "Default")
      (node (ref "U$1") (pin "A5") (pinfunction "A5_A5") (pintype "bidirectional"))
    )
    (net (code "147") (name "unconnected-(U$1-PadA6)") (class "Default")
      (node (ref "U$1") (pin "A6") (pinfunction "A6_A6") (pintype "bidirectional"))
    )
    (net (code "148") (name "unconnected-(U$1-PadA7)") (class "Default")
      (node (ref "U$1") (pin "A7") (pinfunction "A7_A7") (pintype "bidirectional"))
    )
    (net (code "149") (name "unconnected-(U$1-PadAREF)") (class "Default")
      (node (ref "U$1") (pin "AREF") (pinfunction "AREF_AREF") (pintype "bidirectional"))
    )
    (net (code "150") (name "unconnected-(U$1-PadD7)") (class "Default")
      (node (ref "U$1") (pin "D7") (pinfunction "D7_D7") (pintype "bidirectional"))
    )
    (net (code "151") (name "unconnected-(U$1-PadD9)") (class "Default")
      (node (ref "U$1") (pin "D9") (pinfunction "D9_D9") (pintype "bidirectional"))
    )
    (net (code "152") (name "unconnected-(U$1-PadD13)") (class "Default")
      (node (ref "U$1") (pin "D13") (pinfunction "D13_D13") (pintype "bidirectional"))
    )
    (net (code "153") (name "unconnected-(U$1-PadICSP1)") (class "Default")
      (node (ref "U$1") (pin "ICSP1") (pinfunction "ICSP1_ICSP1") (pintype "bidirectional"))
    )
    (net (code "154") (name "unconnected-(U$1-PadICSP2)") (class "Default")
      (node (ref "U$1") (pin "ICSP2") (pinfunction "ICSP2_ICSP2") (pintype "bidirectional"))
    )
    (net (code "155") (name "unconnected-(U$1-PadICSP3)") (class "Default")
      (node (ref "U$1") (pin "ICSP3") (pinfunction "ICSP3_ICSP3") (pintype "bidirectional"))
    )
    (net (code "156") (name "unconnected-(U$1-PadICSP4)") (class "Default")
      (node (ref "U$1") (pin "ICSP4") (pinfunction "ICSP4_ICSP4") (pintype "bidirectional"))
    )
    (net (code "157") (name "unconnected-(U$1-PadICSP5)") (class "Default")
      (node (ref "U$1") (pin "ICSP5") (pinfunction "ICSP5_ICSP5") (pintype "bidirectional"))
    )
    (net (code "158") (name "unconnected-(U$1-PadICSP6)") (class "Default")
      (node (ref "U$1") (pin "ICSP6") (pinfunction "ICSP6_ICSP6") (pintype "bidirectional"))
    )
    (net (code "159") (name "unconnected-(U$1-PadRAW)") (class "Default")
      (node (ref "U$1") (pin "RAW") (pinfunction "RAW_RAW") (pintype "bidirectional"))
    )
    (net (code "160") (name "unconnected-(U$1-PadRST)") (class "Default")
      (node (ref "U$1") (pin "RST") (pinfunction "RST_RST") (pintype "bidirectional"))
    )
    (net (code "161") (name "unconnected-(U$1-PadRST1)") (class "Default")
      (node (ref "U$1") (pin "RST1") (pinfunction "RST1_RST1") (pintype "bidirectional"))
    )
    (net (code "162") (name "unconnected-(U$1-PadRX1)") (class "Default")
      (node (ref "U$1") (pin "RX1") (pinfunction "RX1_RX1") (pintype "bidirectional"))
    )
    (net (code "163") (name "unconnected-(U$1-PadTX0)") (class "Default")
      (node (ref "U$1") (pin "TX0") (pinfunction "TX0_TX0") (pintype "bidirectional"))
    )
    (net (code "164") (name "unconnected-(U$4-A11-Pad12)") (class "Default")
      (node (ref "U$4") (pin "12") (pinfunction "A11_12") (pintype "passive"))
    )
    (net (code "165") (name "unconnected-(U$4-C11-Pad13)") (class "Default")
      (node (ref "U$4") (pin "13") (pinfunction "C11_13") (pintype "passive"))
    )
  )
)
